# circuit_level.net
KiCad netlist of a schematic drawn in Altium Designer
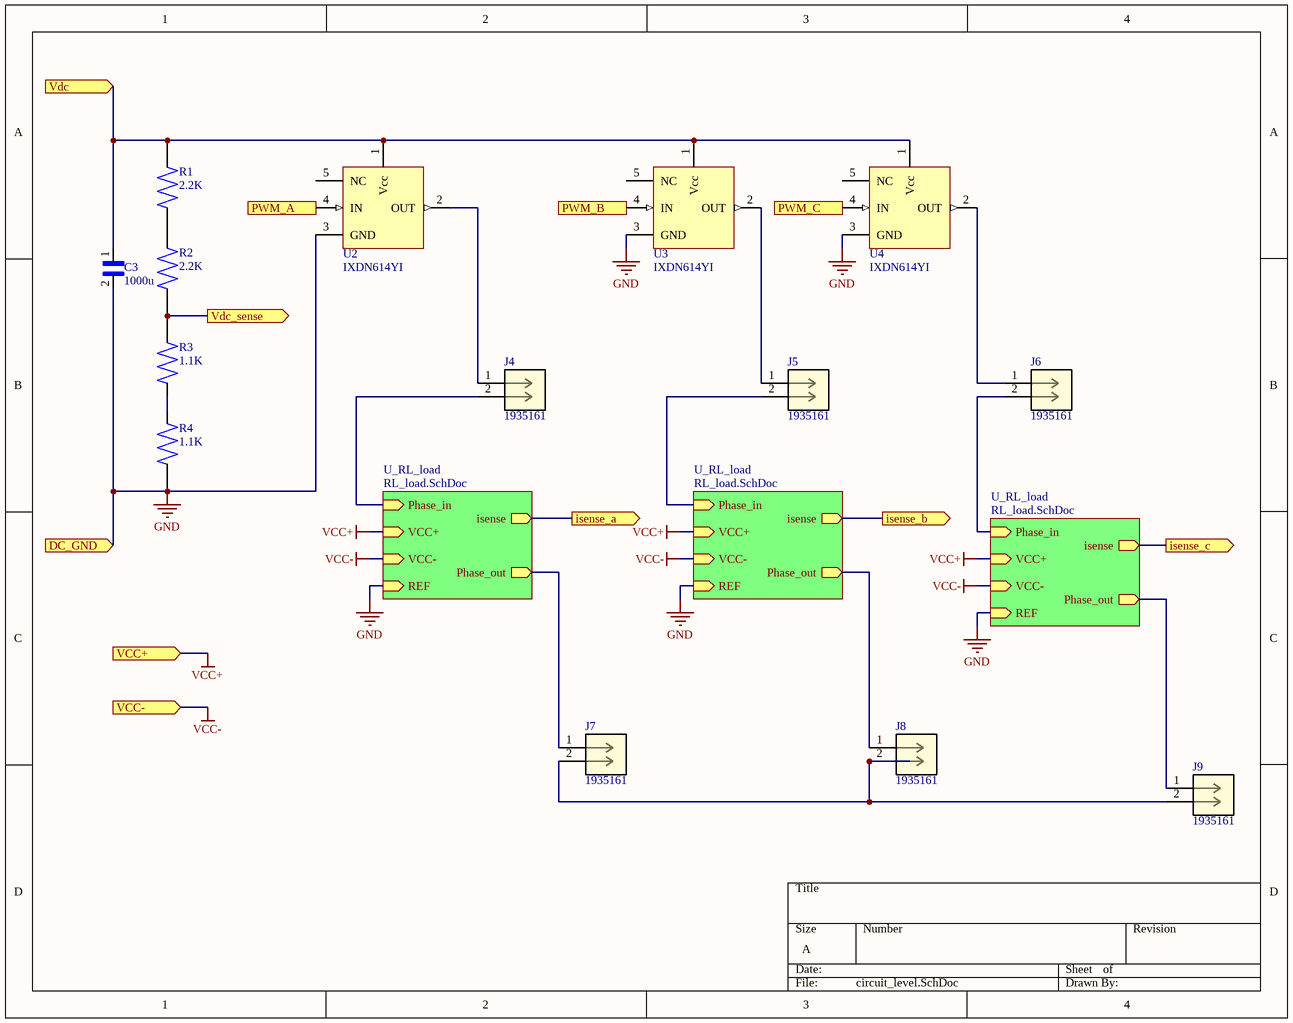
[diagram p0: circuit_level.SchDoc]

(export (version "E")
  (design (tool "Eeschema 10.0.6"))
  (components
    (comp (ref "C3")
      (value "1000u")
      (description "Cap Aluminum 1000uF 35V 20% (12.5 X 25mm) Radial 5mm 3190mA 7000 hr 105C Ammo Pack")
      (fields
        (field (name "MANUFACTURER") "Panasonic")
        (field (name "MANUFACTURER PART NUMBER") "EEU-FM1V102B")
      )
      (libsource (lib "Schlib_uInv01") (part "EEU-FM1V102B"))
    )
    (comp (ref "J4")
      (value "1935161")
      (description "Conn Terminal Blocks 2 POS 5mm Solder ST Thru-Hole 16A")
      (fields (field (name "MANUFACTURER") "Phoenix Contact") (field (name "VOLTAGE") "300V"))
      (libsource (lib "Schlib_uInv01") (part "1935161"))
    )
    (comp (ref "J5")
      (value "1935161")
      (description "Conn Terminal Blocks 2 POS 5mm Solder ST Thru-Hole 16A")
      (fields (field (name "MANUFACTURER") "Phoenix Contact") (field (name "VOLTAGE") "300V"))
      (libsource (lib "Schlib_uInv01") (part "1935161"))
    )
    (comp (ref "J6")
      (value "1935161")
      (description "Conn Terminal Blocks 2 POS 5mm Solder ST Thru-Hole 16A")
      (fields (field (name "MANUFACTURER") "Phoenix Contact") (field (name "VOLTAGE") "300V"))
      (libsource (lib "Schlib_uInv01") (part "1935161"))
    )
    (comp (ref "J7")
      (value "1935161")
      (description "Conn Terminal Blocks 2 POS 5mm Solder ST Thru-Hole 16A")
      (fields (field (name "MANUFACTURER") "Phoenix Contact") (field (name "VOLTAGE") "300V"))
      (libsource (lib "Schlib_uInv01") (part "1935161"))
    )
    (comp (ref "J8")
      (value "1935161")
      (description "Conn Terminal Blocks 2 POS 5mm Solder ST Thru-Hole 16A")
      (fields (field (name "MANUFACTURER") "Phoenix Contact") (field (name "VOLTAGE") "300V"))
      (libsource (lib "Schlib_uInv01") (part "1935161"))
    )
    (comp (ref "J9")
      (value "1935161")
      (description "Conn Terminal Blocks 2 POS 5mm Solder ST Thru-Hole 16A")
      (fields (field (name "MANUFACTURER") "Phoenix Contact") (field (name "VOLTAGE") "300V"))
      (libsource (lib "Schlib_uInv01") (part "1935161"))
    )
    (comp (ref "R1")
      (value "2.2K")
      (description "Res Thick Film 0603 2.49K Ohm 1% 1/4W ±100ppm/°C Molded SMD Paper T/R")
      (fields
        (field (name "MANUFACTURER") "Vishay Dale")
        (field (name "MANUFACTURER PART NUMBER") "RCS06032K49FKEA")
      )
      (libsource (lib "Schlib_uInv01") (part "RCS06032K49FKEA"))
    )
    (comp (ref "R2")
      (value "2.2K")
      (description "Res Thick Film 0603 2.49K Ohm 1% 1/4W ±100ppm/°C Molded SMD Paper T/R")
      (fields
        (field (name "MANUFACTURER") "Vishay Dale")
        (field (name "MANUFACTURER PART NUMBER") "RCS06032K49FKEA")
      )
      (libsource (lib "Schlib_uInv01") (part "RCS06032K49FKEA"))
    )
    (comp (ref "R3")
      (value "1.1K")
      (description "RES SMD 1.1K OHM 1% 1/4W 0603")
      (fields
        (field (name "MANUFACTURER") "Vishay Dale")
        (field (name "MANUFACTURER PART NUMBER") "RCS06031K10FKEA")
      )
      (libsource (lib "Schlib_uInv01") (part "RCS06031K10FKEA"))
    )
    (comp (ref "R4")
      (value "1.1K")
      (description "RES SMD 1.1K OHM 1% 1/4W 0603")
      (fields
        (field (name "MANUFACTURER") "Vishay Dale")
        (field (name "MANUFACTURER PART NUMBER") "RCS06031K10FKEA")
      )
      (libsource (lib "Schlib_uInv01") (part "RCS06031K10FKEA"))
    )
    (comp (ref "U2")
      (value "IXDN614YI")
      (description "14-Ampere Low-Side Ultrafast Mosfet Driver 5-Lead To-263 Rohs Compliant: Yes")
      (fields (field (name "MANUFACTURER") "Ixys Clare"))
      (libsource (lib "Schlib_uInv01") (part "IXDN614YI"))
    )
    (comp (ref "U3")
      (value "IXDN614YI")
      (description "14-Ampere Low-Side Ultrafast Mosfet Driver 5-Lead To-263 Rohs Compliant: Yes")
      (fields (field (name "MANUFACTURER") "Ixys Clare"))
      (libsource (lib "Schlib_uInv01") (part "IXDN614YI"))
    )
    (comp (ref "U4")
      (value "IXDN614YI")
      (description "14-Ampere Low-Side Ultrafast Mosfet Driver 5-Lead To-263 Rohs Compliant: Yes")
      (fields (field (name "MANUFACTURER") "Ixys Clare"))
      (libsource (lib "Schlib_uInv01") (part "IXDN614YI"))
    )
  )
  (nets
    (net (code "1") (name "/PWM_A") (class "Default")
      (node (ref "U2") (pin "4") (pinfunction "IN_4") (pintype "input"))
    )
    (net (code "2") (name "/PWM_B") (class "Default")
      (node (ref "U3") (pin "4") (pinfunction "IN_4") (pintype "input"))
    )
    (net (code "3") (name "/PWM_C") (class "Default")
      (node (ref "U4") (pin "4") (pinfunction "IN_4") (pintype "input"))
    )
    (net (code "4") (name "/Phase_in") (class "Default")
      (node (ref "J5") (pin "2") (pinfunction "2_2") (pintype "passive"))
    )
    (net (code "5") (name "/Phase_in_1") (class "Default")
      (node (ref "J4") (pin "2") (pinfunction "2_2") (pintype "passive"))
    )
    (net (code "6") (name "/Phase_in_2") (class "Default")
      (node (ref "J6") (pin "2") (pinfunction "2_2") (pintype "passive"))
    )
    (net (code "7") (name "/Phase_out") (class "Default")
      (node (ref "J7") (pin "1") (pinfunction "1_1") (pintype "passive"))
    )
    (net (code "8") (name "/Phase_out_1") (class "Default")
      (node (ref "J8") (pin "1") (pinfunction "1_1") (pintype "passive"))
    )
    (net (code "9") (name "/Phase_out_2") (class "Default")
      (node (ref "J9") (pin "1") (pinfunction "1_1") (pintype "passive"))
    )
    (net (code "10") (name "/Vdc") (class "Default")
      (node (ref "C3") (pin "1") (pinfunction "1_1") (pintype "passive"))
      (node (ref "R1") (pin "1") (pinfunction "1_1") (pintype "passive"))
      (node (ref "U2") (pin "1") (pinfunction "Vcc_1") (pintype "power_in"))
      (node (ref "U3") (pin "1") (pinfunction "Vcc_1") (pintype "power_in"))
      (node (ref "U4") (pin "1") (pinfunction "Vcc_1") (pintype "power_in"))
    )
    (net (code "11") (name "/Vdc_sense") (class "Default")
      (node (ref "R2") (pin "2") (pinfunction "2_2") (pintype "passive"))
      (node (ref "R3") (pin "1") (pinfunction "1_1") (pintype "passive"))
    )
    (net (code "15") (name "GND") (class "Default")
      (node (ref "C3") (pin "2") (pinfunction "2_2") (pintype "passive"))
      (node (ref "R4") (pin "2") (pinfunction "2_2") (pintype "passive"))
      (node (ref "U2") (pin "3") (pinfunction "GND_3") (pintype "power_in"))
      (node (ref "U3") (pin "3") (pinfunction "GND_3") (pintype "power_in"))
      (node (ref "U4") (pin "3") (pinfunction "GND_3") (pintype "power_in"))
    )
    (net (code "16") (name "Net-(J7-Pad2)") (class "Default")
      (node (ref "J7") (pin "2") (pinfunction "2_2") (pintype "passive"))
      (node (ref "J8") (pin "2") (pinfunction "2_2") (pintype "passive"))
      (node (ref "J9") (pin "2") (pinfunction "2_2") (pintype "passive"))
    )
    (net (code "17") (name "Net-(R3-Pad2)") (class "Default")
      (node (ref "R3") (pin "2") (pinfunction "2_2") (pintype "passive"))
      (node (ref "R4") (pin "1") (pinfunction "1_1") (pintype "passive"))
    )
    (net (code "18") (name "Net-(U2-OUT)") (class "Default")
      (node (ref "J4") (pin "1") (pinfunction "1_1") (pintype "passive"))
      (node (ref "U2") (pin "2") (pinfunction "OUT_2") (pintype "output"))
    )
    (net (code "19") (name "Net-(U3-OUT)") (class "Default")
      (node (ref "J5") (pin "1") (pinfunction "1_1") (pintype "passive"))
      (node (ref "U3") (pin "2") (pinfunction "OUT_2") (pintype "output"))
    )
    (net (code "20") (name "Net-(U4-OUT)") (class "Default")
      (node (ref "J6") (pin "1") (pinfunction "1_1") (pintype "passive"))
      (node (ref "U4") (pin "2") (pinfunction "OUT_2") (pintype "output"))
    )
    (net (code "23") (name "unconnected-(R1-Pad2)") (class "Default")
      (node (ref "R1") (pin "2") (pinfunction "2_2") (pintype "passive"))
    )
    (net (code "24") (name "unconnected-(R2-Pad1)") (class "Default")
      (node (ref "R2") (pin "1") (pinfunction "1_1") (pintype "passive"))
    )
    (net (code "25") (name "unconnected-(U2-NC-Pad5)") (class "Default")
      (node (ref "U2") (pin "5") (pinfunction "NC_5") (pintype "passive"))
    )
    (net (code "26") (name "unconnected-(U3-NC-Pad5)") (class "Default")
      (node (ref "U3") (pin "5") (pinfunction "NC_5") (pintype "passive"))
    )
    (net (code "27") (name "unconnected-(U4-NC-Pad5)") (class "Default")
      (node (ref "U4") (pin "5") (pinfunction "NC_5") (pintype "passive"))
    )
  )
)
